# SmartBMSv2.net
KiCad netlist of a schematic drawn in EAGLE
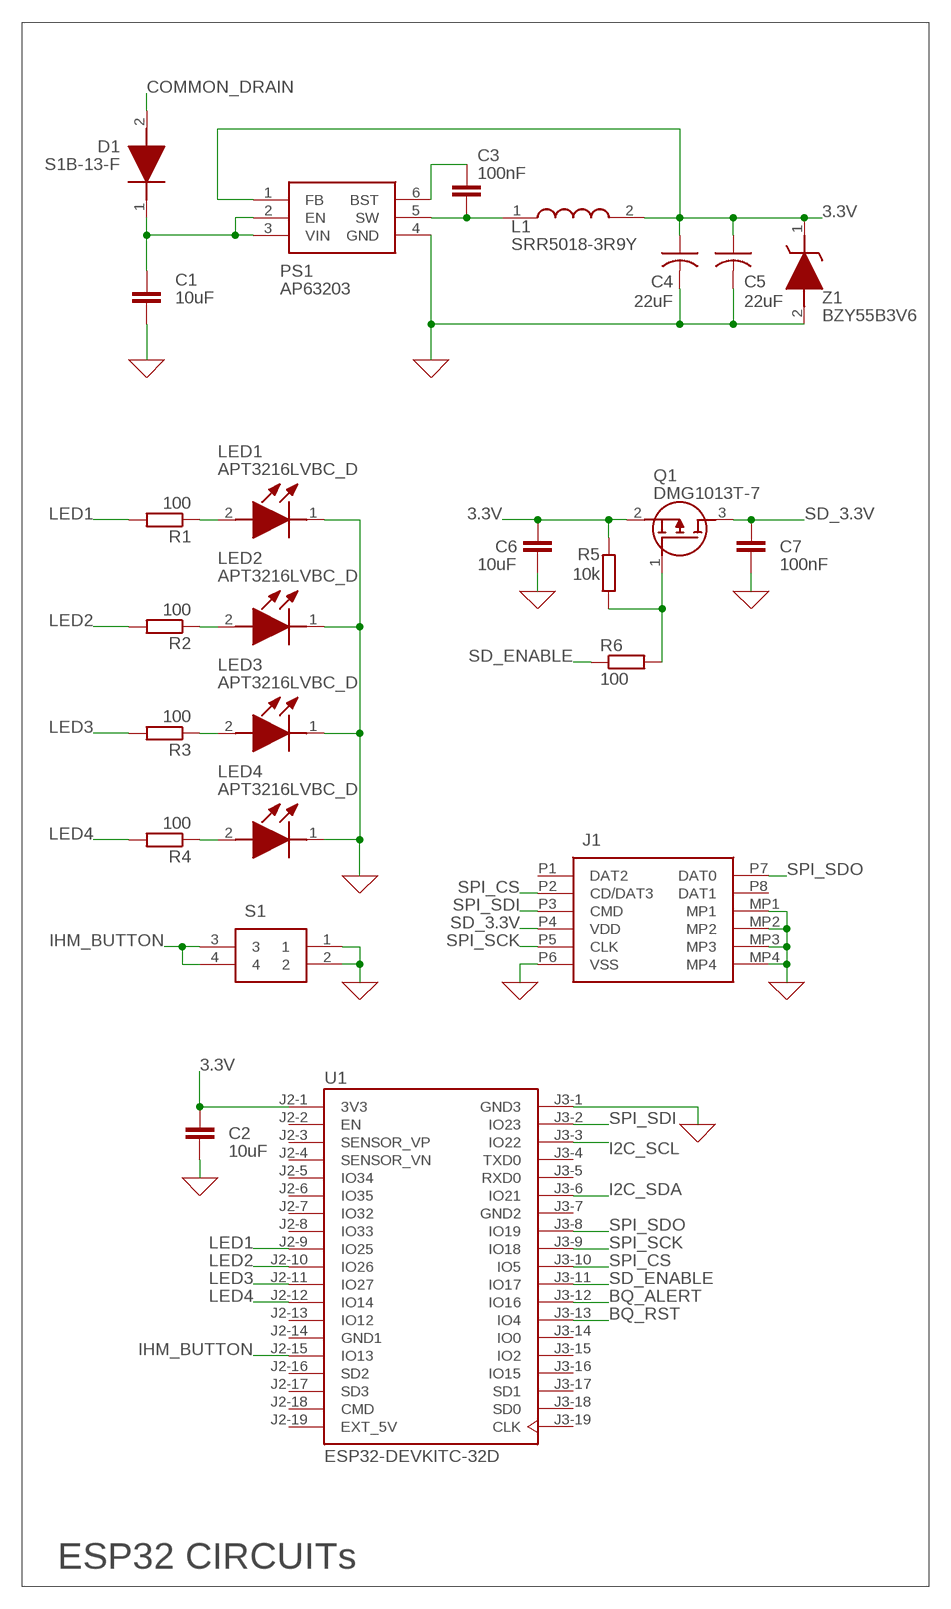
[diagram p0: schematic, sheet 1, part 1 of 2]
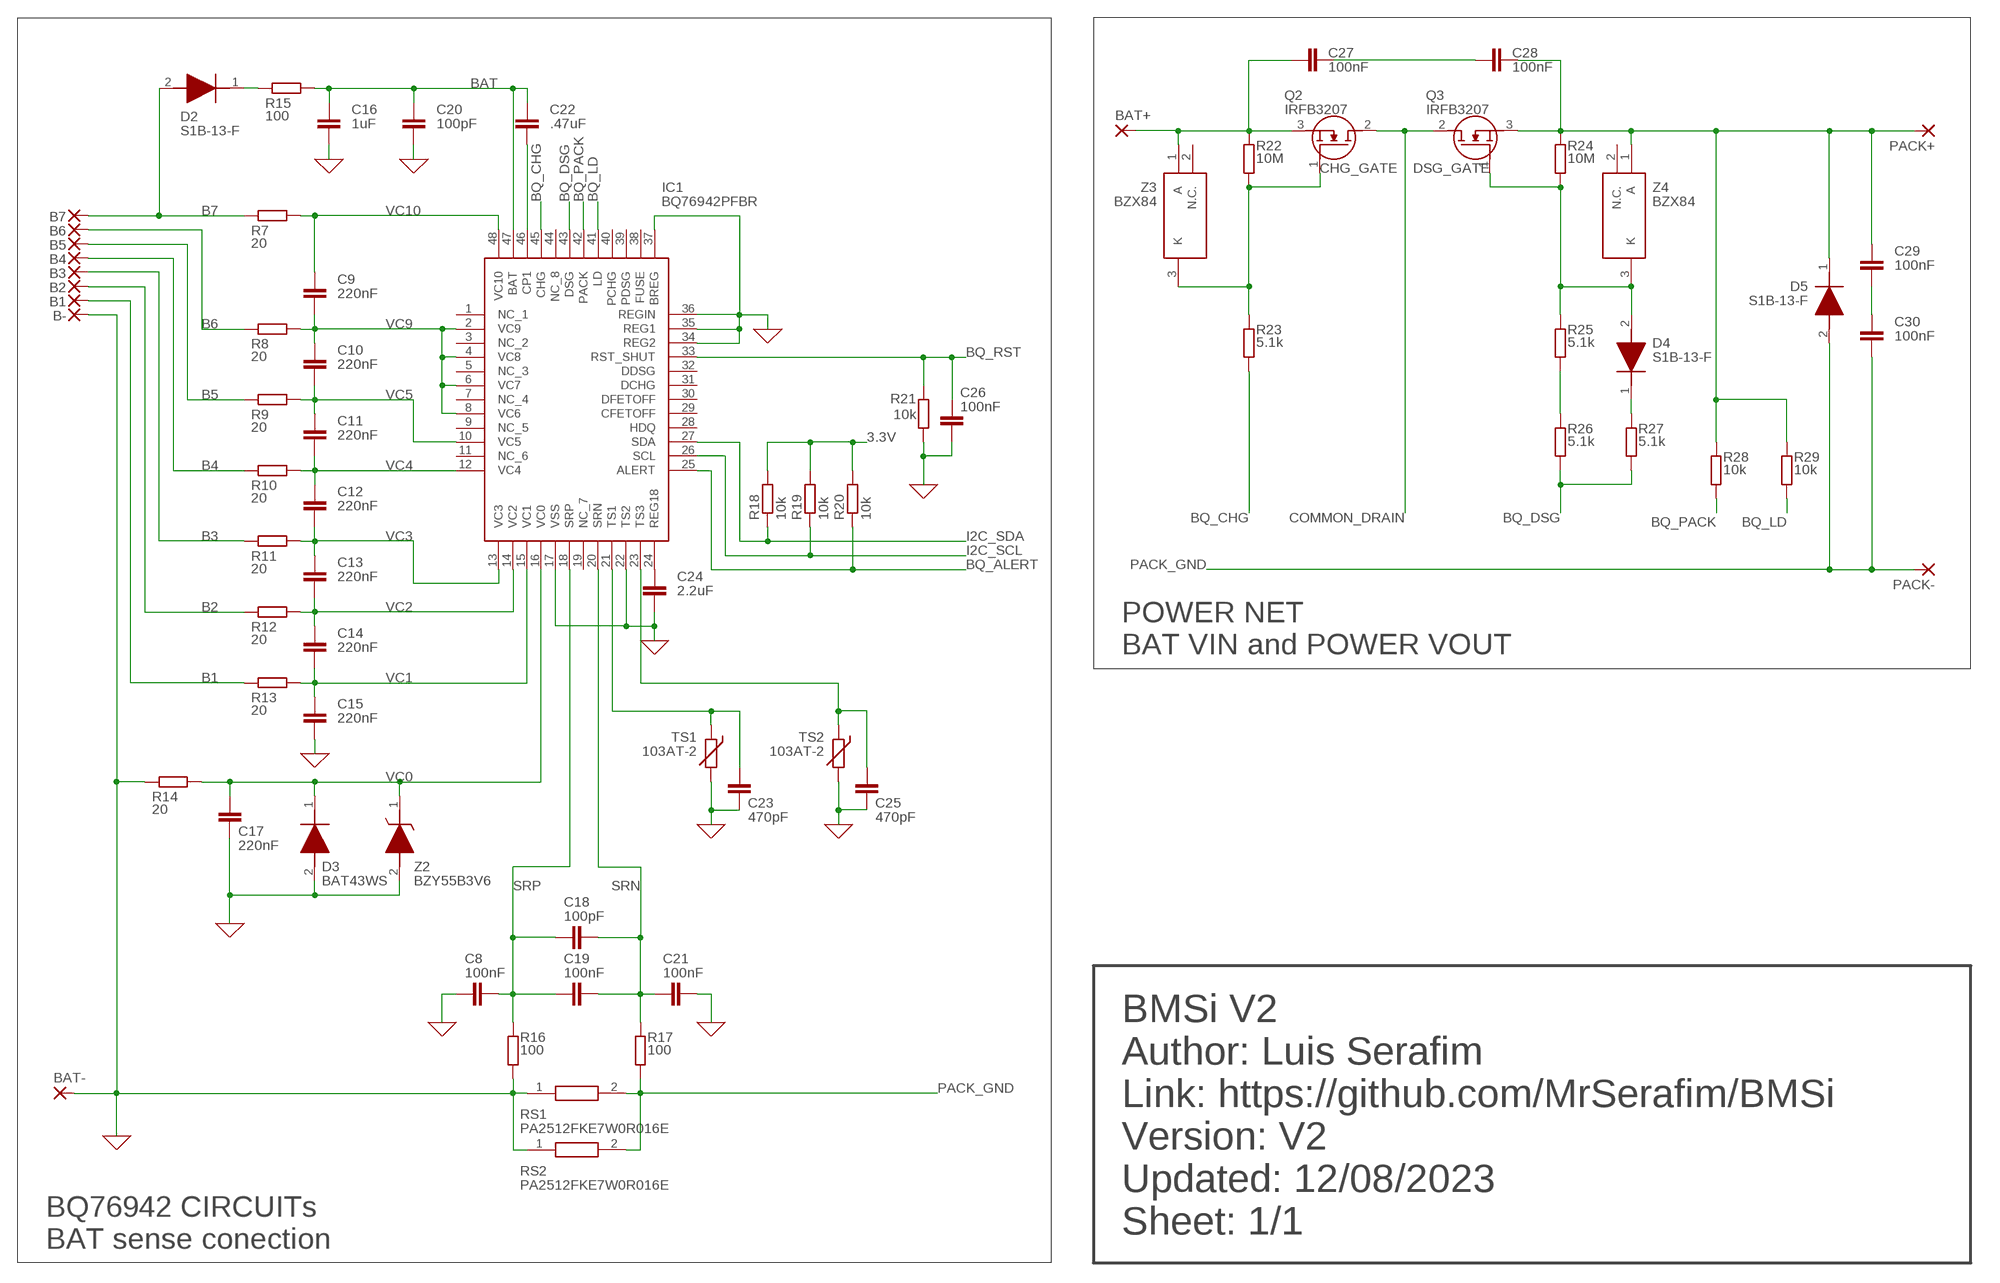
[diagram p1: schematic, sheet 1, part 2 of 2]

(export (version "E")
  (design (tool "Eeschema 10.0.6"))
  (components
    (comp (ref "B-")
      (value "SMD5")
      (footprint "eagle-import:SMD2,54-5,08")
      (libsource (lib "eagle-import") (part "SMD5"))
    )
    (comp (ref "B1")
      (value "SMD5")
      (footprint "eagle-import:SMD2,54-5,08")
      (libsource (lib "eagle-import") (part "SMD5"))
    )
    (comp (ref "B2")
      (value "SMD5")
      (footprint "eagle-import:SMD2,54-5,08")
      (libsource (lib "eagle-import") (part "SMD5"))
    )
    (comp (ref "B3")
      (value "SMD5")
      (footprint "eagle-import:SMD2,54-5,08")
      (libsource (lib "eagle-import") (part "SMD5"))
    )
    (comp (ref "B4")
      (value "SMD5")
      (footprint "eagle-import:SMD2,54-5,08")
      (libsource (lib "eagle-import") (part "SMD5"))
    )
    (comp (ref "B5")
      (value "SMD5")
      (footprint "eagle-import:SMD2,54-5,08")
      (libsource (lib "eagle-import") (part "SMD5"))
    )
    (comp (ref "B6")
      (value "SMD5")
      (footprint "eagle-import:SMD2,54-5,08")
      (libsource (lib "eagle-import") (part "SMD5"))
    )
    (comp (ref "B7")
      (value "SMD5")
      (footprint "eagle-import:SMD2,54-5,08")
      (libsource (lib "eagle-import") (part "SMD5"))
    )
    (comp (ref "BAT+")
      (value "SMD5X10")
      (footprint "eagle-import:SMD5-10")
      (libsource (lib "eagle-import") (part "SMD5X10"))
    )
    (comp (ref "BAT-")
      (value "SMD5X10")
      (footprint "eagle-import:SMD5-10")
      (libsource (lib "eagle-import") (part "SMD5X10"))
    )
    (comp (ref "C1")
      (value "10uF")
      (footprint "eagle-import:C0805")
      (libsource (lib "eagle-import") (part "C-EUC0805"))
    )
    (comp (ref "C2")
      (value "10uF")
      (footprint "eagle-import:C0805")
      (libsource (lib "eagle-import") (part "C-EUC0805"))
    )
    (comp (ref "C3")
      (value "100nF")
      (footprint "eagle-import:C0805")
      (libsource (lib "eagle-import") (part "C-EUC0805"))
    )
    (comp (ref "C4")
      (value "22uF")
      (footprint "eagle-import:C0805")
      (libsource (lib "eagle-import") (part "C-USC0805"))
    )
    (comp (ref "C5")
      (value "22uF")
      (footprint "eagle-import:C0805")
      (libsource (lib "eagle-import") (part "C-USC0805"))
    )
    (comp (ref "C6")
      (value "10uF")
      (footprint "eagle-import:C0805")
      (libsource (lib "eagle-import") (part "C-EUC0805"))
    )
    (comp (ref "C7")
      (value "100nF")
      (footprint "eagle-import:C0805")
      (libsource (lib "eagle-import") (part "C-EUC0805"))
    )
    (comp (ref "C8")
      (value "100nF")
      (footprint "eagle-import:C0805")
      (libsource (lib "eagle-import") (part "C-EUC0805"))
    )
    (comp (ref "C9")
      (value "220nF")
      (footprint "eagle-import:C0805")
      (libsource (lib "eagle-import") (part "C-EUC0805"))
    )
    (comp (ref "C10")
      (value "220nF")
      (footprint "eagle-import:C0805")
      (libsource (lib "eagle-import") (part "C-EUC0805"))
    )
    (comp (ref "C11")
      (value "220nF")
      (footprint "eagle-import:C0805")
      (libsource (lib "eagle-import") (part "C-EUC0805"))
    )
    (comp (ref "C12")
      (value "220nF")
      (footprint "eagle-import:C0805")
      (libsource (lib "eagle-import") (part "C-EUC0805"))
    )
    (comp (ref "C13")
      (value "220nF")
      (footprint "eagle-import:C0805")
      (libsource (lib "eagle-import") (part "C-EUC0805"))
    )
    (comp (ref "C14")
      (value "220nF")
      (footprint "eagle-import:C0805")
      (libsource (lib "eagle-import") (part "C-EUC0805"))
    )
    (comp (ref "C15")
      (value "220nF")
      (footprint "eagle-import:C0805")
      (libsource (lib "eagle-import") (part "C-EUC0805"))
    )
    (comp (ref "C16")
      (value "1uF")
      (footprint "eagle-import:C0805")
      (libsource (lib "eagle-import") (part "C-EUC0805"))
    )
    (comp (ref "C17")
      (value "220nF")
      (footprint "eagle-import:C0805")
      (libsource (lib "eagle-import") (part "C-EUC0805"))
    )
    (comp (ref "C18")
      (value "100pF")
      (footprint "eagle-import:C0805")
      (libsource (lib "eagle-import") (part "C-EUC0805"))
    )
    (comp (ref "C19")
      (value "100nF")
      (footprint "eagle-import:C0805")
      (libsource (lib "eagle-import") (part "C-EUC0805"))
    )
    (comp (ref "C20")
      (value "100pF")
      (footprint "eagle-import:C0805")
      (libsource (lib "eagle-import") (part "C-EUC0805"))
    )
    (comp (ref "C21")
      (value "100nF")
      (footprint "eagle-import:C0805")
      (libsource (lib "eagle-import") (part "C-EUC0805"))
    )
    (comp (ref "C22")
      (value ".47uF")
      (footprint "eagle-import:C0805")
      (libsource (lib "eagle-import") (part "C-EUC0805"))
    )
    (comp (ref "C23")
      (value "470pF")
      (footprint "eagle-import:C0805")
      (libsource (lib "eagle-import") (part "C-EUC0805"))
    )
    (comp (ref "C24")
      (value "2.2uF")
      (footprint "eagle-import:C0805")
      (libsource (lib "eagle-import") (part "C-EUC0805"))
    )
    (comp (ref "C25")
      (value "470pF")
      (footprint "eagle-import:C0805")
      (libsource (lib "eagle-import") (part "C-EUC0805"))
    )
    (comp (ref "C26")
      (value "100nF")
      (footprint "eagle-import:C0805")
      (libsource (lib "eagle-import") (part "C-EUC0805"))
    )
    (comp (ref "C27")
      (value "100nF")
      (footprint "eagle-import:C0805")
      (libsource (lib "eagle-import") (part "C-EUC0805"))
    )
    (comp (ref "C28")
      (value "100nF")
      (footprint "eagle-import:C0805")
      (libsource (lib "eagle-import") (part "C-EUC0805"))
    )
    (comp (ref "C29")
      (value "100nF")
      (footprint "eagle-import:C0805")
      (libsource (lib "eagle-import") (part "C-EUC0805"))
    )
    (comp (ref "C30")
      (value "100nF")
      (footprint "eagle-import:C0805")
      (libsource (lib "eagle-import") (part "C-EUC0805"))
    )
    (comp (ref "D1")
      (value "S1B-13-F")
      (footprint "eagle-import:DIONM5126X230N")
      (fields (field (name "MOUSER_PART_NUMBER") "621-S1B-F"))
      (libsource (lib "eagle-import") (part "S1B-13-F"))
    )
    (comp (ref "D2")
      (value "S1B-13-F")
      (footprint "eagle-import:DIONM5126X230N")
      (fields (field (name "MOUSER_PART_NUMBER") "621-S1B-F"))
      (libsource (lib "eagle-import") (part "S1B-13-F"))
    )
    (comp (ref "D3")
      (value "BAT43WS")
      (footprint "eagle-import:SOD2713X115N")
      (fields
        (field (name "MANUFACTURER_PART_NUMBER") "BAT43WS-E3-08")
        (field (name "MOUSER_PART_NUMBER") "78-BAT43WS-E3-08")
      )
      (libsource (lib "eagle-import") (part "BAT43WS-E3-08"))
    )
    (comp (ref "D4")
      (value "S1B-13-F")
      (footprint "eagle-import:DIONM5126X230N")
      (fields (field (name "MOUSER_PART_NUMBER") "621-S1B-F"))
      (libsource (lib "eagle-import") (part "S1B-13-F"))
    )
    (comp (ref "D5")
      (value "S1B-13-F")
      (footprint "eagle-import:DIONM5126X230N")
      (fields (field (name "MOUSER_PART_NUMBER") "621-S1B-F"))
      (libsource (lib "eagle-import") (part "S1B-13-F"))
    )
    (comp (ref "IC1")
      (value "BQ76942PFBR")
      (footprint "eagle-import:QFP50P900X900X120-48N")
      (fields (field (name "MOUSER_PART_NUMBER") "595-BQ76942PFBR"))
      (libsource (lib "eagle-import") (part "BQ76942PFBR"))
    )
    (comp (ref "J1")
      (value "MEM2067-02-180-00-A")
      (footprint "eagle-import:MEM20670218000A")
      (fields (field (name "MOUSER_PART_NUMBER") "640-MEM20670218000A"))
      (libsource (lib "eagle-import") (part "MEM2067-02-180-00-A"))
    )
    (comp (ref "L1")
      (value "SRR5018-3R9Y")
      (footprint "eagle-import:SRR50183R9Y")
      (fields (field (name "MOUSER_PART_NUMBER") "652-SRR5018-3R9Y"))
      (libsource (lib "eagle-import") (part "SRR5018-3R9Y"))
    )
    (comp (ref "LED1")
      (value "APT3216LVBC_D")
      (footprint "eagle-import:LEDC3216X95N")
      (fields
        (field (name "MANUFACTURER_PART_NUMBER") "APT3216LVBC/D")
        (field (name "MOUSER_PART_NUMBER") "604-APT3216LVBCD")
      )
      (libsource (lib "eagle-import") (part "APT3216LVBC_D"))
    )
    (comp (ref "LED2")
      (value "APT3216LVBC_D")
      (footprint "eagle-import:LEDC3216X95N")
      (fields
        (field (name "MANUFACTURER_PART_NUMBER") "APT3216LVBC/D")
        (field (name "MOUSER_PART_NUMBER") "604-APT3216LVBCD")
      )
      (libsource (lib "eagle-import") (part "APT3216LVBC_D"))
    )
    (comp (ref "LED3")
      (value "APT3216LVBC_D")
      (footprint "eagle-import:LEDC3216X95N")
      (fields
        (field (name "MANUFACTURER_PART_NUMBER") "APT3216LVBC/D")
        (field (name "MOUSER_PART_NUMBER") "604-APT3216LVBCD")
      )
      (libsource (lib "eagle-import") (part "APT3216LVBC_D"))
    )
    (comp (ref "LED4")
      (value "APT3216LVBC_D")
      (footprint "eagle-import:LEDC3216X95N")
      (fields
        (field (name "MANUFACTURER_PART_NUMBER") "APT3216LVBC/D")
        (field (name "MOUSER_PART_NUMBER") "604-APT3216LVBCD")
      )
      (libsource (lib "eagle-import") (part "APT3216LVBC_D"))
    )
    (comp (ref "PACK+")
      (value "SMD5X10")
      (footprint "eagle-import:SMD5-10")
      (libsource (lib "eagle-import") (part "SMD5X10"))
    )
    (comp (ref "PACK-")
      (value "SMD5X10")
      (footprint "eagle-import:SMD5-10")
      (libsource (lib "eagle-import") (part "SMD5X10"))
    )
    (comp (ref "PS1")
      (value "AP63203")
      (footprint "eagle-import:SOT95P280X100-6N")
      (fields
        (field (name "MANUFACTURER_PART_NUMBER") "AP63203WU-7")
        (field (name "MOUSER_PART_NUMBER") "621-AP63203WU-7")
      )
      (libsource (lib "eagle-import") (part "AP63203WU-7"))
    )
    (comp (ref "Q1")
      (value "DMG1013T-7")
      (footprint "eagle-import:SOT50P160X90-3N")
      (fields (field (name "MOUSER_PART_NUMBER") "621-DMG1013T-7"))
      (libsource (lib "eagle-import") (part "DMG1013T-7"))
    )
    (comp (ref "Q2")
      (value "IRFB3207")
      (footprint "eagle-import:TO220_HORIZONTAL")
      (libsource (lib "eagle-import") (part "IRFB3207PBF_HOR"))
    )
    (comp (ref "Q3")
      (value "IRFB3207")
      (footprint "eagle-import:TO220_HORIZONTAL")
      (libsource (lib "eagle-import") (part "IRFB3207PBF_HOR"))
    )
    (comp (ref "R1")
      (value "100")
      (footprint "eagle-import:R0805")
      (libsource (lib "eagle-import") (part "R-EU_R0805"))
    )
    (comp (ref "R2")
      (value "100")
      (footprint "eagle-import:R0805")
      (libsource (lib "eagle-import") (part "R-EU_R0805"))
    )
    (comp (ref "R3")
      (value "100")
      (footprint "eagle-import:R0805")
      (libsource (lib "eagle-import") (part "R-EU_R0805"))
    )
    (comp (ref "R4")
      (value "100")
      (footprint "eagle-import:R0805")
      (libsource (lib "eagle-import") (part "R-EU_R0805"))
    )
    (comp (ref "R5")
      (value "10k")
      (footprint "eagle-import:R0805")
      (libsource (lib "eagle-import") (part "R-EU_R0805"))
    )
    (comp (ref "R6")
      (value "100")
      (footprint "eagle-import:R0805")
      (libsource (lib "eagle-import") (part "R-EU_R0805"))
    )
    (comp (ref "R7")
      (value "20")
      (footprint "eagle-import:R0805")
      (libsource (lib "eagle-import") (part "R-EU_R0805"))
    )
    (comp (ref "R8")
      (value "20")
      (footprint "eagle-import:R0805")
      (libsource (lib "eagle-import") (part "R-EU_R0805"))
    )
    (comp (ref "R9")
      (value "20")
      (footprint "eagle-import:R0805")
      (libsource (lib "eagle-import") (part "R-EU_R0805"))
    )
    (comp (ref "R10")
      (value "20")
      (footprint "eagle-import:R0805")
      (libsource (lib "eagle-import") (part "R-EU_R0805"))
    )
    (comp (ref "R11")
      (value "20")
      (footprint "eagle-import:R0805")
      (libsource (lib "eagle-import") (part "R-EU_R0805"))
    )
    (comp (ref "R12")
      (value "20")
      (footprint "eagle-import:R0805")
      (libsource (lib "eagle-import") (part "R-EU_R0805"))
    )
    (comp (ref "R13")
      (value "20")
      (footprint "eagle-import:R0805")
      (libsource (lib "eagle-import") (part "R-EU_R0805"))
    )
    (comp (ref "R14")
      (value "20")
      (footprint "eagle-import:R0805")
      (libsource (lib "eagle-import") (part "R-EU_R0805"))
    )
    (comp (ref "R15")
      (value "100")
      (footprint "eagle-import:R0805")
      (libsource (lib "eagle-import") (part "R-EU_R0805"))
    )
    (comp (ref "R16")
      (value "100")
      (footprint "eagle-import:R0805")
      (libsource (lib "eagle-import") (part "R-EU_R0805"))
    )
    (comp (ref "R17")
      (value "100")
      (footprint "eagle-import:R0805")
      (libsource (lib "eagle-import") (part "R-EU_R0805"))
    )
    (comp (ref "R18")
      (value "10k")
      (footprint "eagle-import:R0805")
      (libsource (lib "eagle-import") (part "R-EU_R0805"))
    )
    (comp (ref "R19")
      (value "10k")
      (footprint "eagle-import:R0805")
      (libsource (lib "eagle-import") (part "R-EU_R0805"))
    )
    (comp (ref "R20")
      (value "10k")
      (footprint "eagle-import:R0805")
      (libsource (lib "eagle-import") (part "R-EU_R0805"))
    )
    (comp (ref "R21")
      (value "10k")
      (footprint "eagle-import:R0805")
      (libsource (lib "eagle-import") (part "R-EU_R0805"))
    )
    (comp (ref "R22")
      (value "10M")
      (footprint "eagle-import:R0805")
      (libsource (lib "eagle-import") (part "R-EU_R0805"))
    )
    (comp (ref "R23")
      (value "5.1k")
      (footprint "eagle-import:R0805")
      (libsource (lib "eagle-import") (part "R-EU_R0805"))
    )
    (comp (ref "R24")
      (value "10M")
      (footprint "eagle-import:R0805")
      (libsource (lib "eagle-import") (part "R-EU_R0805"))
    )
    (comp (ref "R25")
      (value "5.1k")
      (footprint "eagle-import:R0805")
      (libsource (lib "eagle-import") (part "R-EU_R0805"))
    )
    (comp (ref "R26")
      (value "5.1k")
      (footprint "eagle-import:R0805")
      (libsource (lib "eagle-import") (part "R-EU_R0805"))
    )
    (comp (ref "R27")
      (value "5.1k")
      (footprint "eagle-import:R0805")
      (libsource (lib "eagle-import") (part "R-EU_R0805"))
    )
    (comp (ref "R28")
      (value "10k")
      (footprint "eagle-import:R0805")
      (libsource (lib "eagle-import") (part "R-EU_R0805"))
    )
    (comp (ref "R29")
      (value "10k")
      (footprint "eagle-import:R0805")
      (libsource (lib "eagle-import") (part "R-EU_R0805"))
    )
    (comp (ref "RS1")
      (value "PA2512FKE7W0R016E")
      (footprint "eagle-import:RESC6432X88N")
      (libsource (lib "eagle-import") (part "PA2512FKE7W0R016E"))
    )
    (comp (ref "RS2")
      (value "PA2512FKE7W0R016E")
      (footprint "eagle-import:RESC6432X88N")
      (libsource (lib "eagle-import") (part "PA2512FKE7W0R016E"))
    )
    (comp (ref "S1")
      (value "FSM2JSMAATR")
      (footprint "eagle-import:FSM2J_1")
      (fields (field (name "MOUSER_PART_NUMBER") "506-FSM2JSMAATR"))
      (libsource (lib "eagle-import") (part "FSM2JSMAATR"))
    )
    (comp (ref "TS1")
      (value "103AT-2")
      (footprint "eagle-import:RS-2,5")
      (libsource (lib "eagle-import") (part "THERMISTOR-2,5"))
    )
    (comp (ref "TS2")
      (value "103AT-2")
      (footprint "eagle-import:RS-2,5")
      (libsource (lib "eagle-import") (part "THERMISTOR-2,5"))
    )
    (comp (ref "U1")
      (value "ESP32-DEVKITC-32D")
      (footprint "eagle-import:MODULE_ESP32-DEVKITC-32D")
      (fields (field (name "MF") "Espressif Systems"))
      (libsource (lib "eagle-import") (part "ESP32-DEVKITC-32D"))
    )
    (comp (ref "Z1")
      (value "BZY55B3V6")
      (footprint "eagle-import:DIOC2012X85N")
      (fields
        (field (name "MANUFACTURER_PART_NUMBER") "BZY55B3V6 RBG")
        (field (name "MOUSER_PART_NUMBER") "821-BZY55B3V6RBG")
      )
      (libsource (lib "eagle-import") (part "BZY55B3V6_RBG"))
    )
    (comp (ref "Z2")
      (value "BZY55B3V6")
      (footprint "eagle-import:DIOC2012X85N")
      (fields
        (field (name "MANUFACTURER_PART_NUMBER") "BZY55B3V6 RBG")
        (field (name "MOUSER_PART_NUMBER") "821-BZY55B3V6RBG")
      )
      (libsource (lib "eagle-import") (part "BZY55B3V6_RBG"))
    )
    (comp (ref "Z3")
      (value "BZX84")
      (footprint "eagle-import:SOT95P230X110-3N")
      (fields
        (field (name "MANUFACTURER_PART_NUMBER") "BZX84-C16,215")
        (field (name "MOUSER_PART_NUMBER") "771-BZX84-C16-T/R")
      )
      (libsource (lib "eagle-import") (part "BZX84-C16,215"))
    )
    (comp (ref "Z4")
      (value "BZX84")
      (footprint "eagle-import:SOT95P230X110-3N")
      (fields
        (field (name "MANUFACTURER_PART_NUMBER") "BZX84-C16,215")
        (field (name "MOUSER_PART_NUMBER") "771-BZX84-C16-T/R")
      )
      (libsource (lib "eagle-import") (part "BZX84-C16,215"))
    )
  )
  (nets
    (net (code "1") (name "/3.3V") (class "Default")
      (node (ref "C2") (pin "1") (pinfunction "1_1") (pintype "passive"))
      (node (ref "C4") (pin "1") (pinfunction "1_1") (pintype "passive"))
      (node (ref "C5") (pin "1") (pinfunction "1_1") (pintype "passive"))
      (node (ref "C6") (pin "2") (pinfunction "2_2") (pintype "passive"))
      (node (ref "L1") (pin "2") (pinfunction "2_2") (pintype "bidirectional"))
      (node (ref "PS1") (pin "1") (pinfunction "FB_1") (pintype "input"))
      (node (ref "Q1") (pin "2") (pinfunction "S_2") (pintype "bidirectional"))
      (node (ref "R18") (pin "2") (pinfunction "2_2") (pintype "passive"))
      (node (ref "R19") (pin "2") (pinfunction "2_2") (pintype "passive"))
      (node (ref "R20") (pin "2") (pinfunction "2_2") (pintype "passive"))
      (node (ref "R5") (pin "2") (pinfunction "2_2") (pintype "passive"))
      (node (ref "U1") (pin "J2-1") (pinfunction "3V3_J2-1") (pintype "power_in"))
      (node (ref "Z1") (pin "1") (pinfunction "K_1") (pintype "bidirectional"))
    )
    (net (code "2") (name "/B1") (class "Default")
      (node (ref "B1") (pin "1") (pinfunction "P_1") (pintype "passive"))
      (node (ref "R13") (pin "1") (pinfunction "1_1") (pintype "passive"))
    )
    (net (code "3") (name "/B2") (class "Default")
      (node (ref "B2") (pin "1") (pinfunction "P_1") (pintype "passive"))
      (node (ref "R12") (pin "1") (pinfunction "1_1") (pintype "passive"))
    )
    (net (code "4") (name "/B3") (class "Default")
      (node (ref "B3") (pin "1") (pinfunction "P_1") (pintype "passive"))
      (node (ref "R11") (pin "1") (pinfunction "1_1") (pintype "passive"))
    )
    (net (code "5") (name "/B4") (class "Default")
      (node (ref "B4") (pin "1") (pinfunction "P_1") (pintype "passive"))
      (node (ref "R10") (pin "1") (pinfunction "1_1") (pintype "passive"))
    )
    (net (code "6") (name "/B5") (class "Default")
      (node (ref "B5") (pin "1") (pinfunction "P_1") (pintype "passive"))
      (node (ref "R9") (pin "1") (pinfunction "1_1") (pintype "passive"))
    )
    (net (code "7") (name "/B6") (class "Default")
      (node (ref "B6") (pin "1") (pinfunction "P_1") (pintype "passive"))
      (node (ref "R8") (pin "1") (pinfunction "1_1") (pintype "passive"))
    )
    (net (code "8") (name "/B7") (class "Default")
      (node (ref "B7") (pin "1") (pinfunction "P_1") (pintype "passive"))
      (node (ref "D2") (pin "2") (pinfunction "A_2") (pintype "bidirectional"))
      (node (ref "R7") (pin "1") (pinfunction "1_1") (pintype "passive"))
    )
    (net (code "9") (name "/BAT") (class "Default")
      (node (ref "C16") (pin "1") (pinfunction "1_1") (pintype "passive"))
      (node (ref "C20") (pin "1") (pinfunction "1_1") (pintype "passive"))
      (node (ref "C22") (pin "1") (pinfunction "1_1") (pintype "passive"))
      (node (ref "IC1") (pin "47") (pinfunction "BAT_47") (pintype "bidirectional"))
      (node (ref "R15") (pin "2") (pinfunction "2_2") (pintype "passive"))
    )
    (net (code "10") (name "/BQ_ALERT") (class "Default")
      (node (ref "IC1") (pin "25") (pinfunction "ALERT_25") (pintype "bidirectional"))
      (node (ref "R20") (pin "1") (pinfunction "1_1") (pintype "passive"))
      (node (ref "U1") (pin "J3-12") (pinfunction "IO16_J3-12") (pintype "bidirectional"))
    )
    (net (code "11") (name "/BQ_CHG") (class "Default")
      (node (ref "IC1") (pin "45") (pinfunction "CHG_45") (pintype "bidirectional"))
      (node (ref "R23") (pin "1") (pinfunction "1_1") (pintype "passive"))
    )
    (net (code "12") (name "/BQ_DSG") (class "Default")
      (node (ref "IC1") (pin "43") (pinfunction "DSG_43") (pintype "bidirectional"))
      (node (ref "R26") (pin "1") (pinfunction "1_1") (pintype "passive"))
      (node (ref "R27") (pin "1") (pinfunction "1_1") (pintype "passive"))
    )
    (net (code "13") (name "/BQ_LD") (class "Default")
      (node (ref "IC1") (pin "41") (pinfunction "LD_41") (pintype "bidirectional"))
      (node (ref "R29") (pin "2") (pinfunction "2_2") (pintype "passive"))
    )
    (net (code "14") (name "/BQ_PACK") (class "Default")
      (node (ref "IC1") (pin "42") (pinfunction "PACK_42") (pintype "bidirectional"))
      (node (ref "R28") (pin "2") (pinfunction "2_2") (pintype "passive"))
    )
    (net (code "15") (name "/BQ_RST") (class "Default")
      (node (ref "C26") (pin "1") (pinfunction "1_1") (pintype "passive"))
      (node (ref "IC1") (pin "33") (pinfunction "RST_SHUT_33") (pintype "bidirectional"))
      (node (ref "R21") (pin "2") (pinfunction "2_2") (pintype "passive"))
      (node (ref "U1") (pin "J3-13") (pinfunction "IO4_J3-13") (pintype "bidirectional"))
    )
    (net (code "16") (name "/CHG_GATE") (class "Default")
      (node (ref "Q2") (pin "1") (pinfunction "G_1") (pintype "bidirectional"))
      (node (ref "R22") (pin "1") (pinfunction "1_1") (pintype "passive"))
      (node (ref "R23") (pin "2") (pinfunction "2_2") (pintype "passive"))
      (node (ref "Z3") (pin "3") (pinfunction "K_3") (pintype "bidirectional"))
    )
    (net (code "17") (name "/COMMON_DRAIN") (class "Default")
      (node (ref "D1") (pin "2") (pinfunction "A_2") (pintype "bidirectional"))
      (node (ref "Q2") (pin "2") (pinfunction "D_2") (pintype "bidirectional"))
      (node (ref "Q3") (pin "2") (pinfunction "D_2") (pintype "bidirectional"))
    )
    (net (code "18") (name "/DSG_GATE") (class "Default")
      (node (ref "D4") (pin "2") (pinfunction "A_2") (pintype "bidirectional"))
      (node (ref "Q3") (pin "1") (pinfunction "G_1") (pintype "bidirectional"))
      (node (ref "R24") (pin "1") (pinfunction "1_1") (pintype "passive"))
      (node (ref "R25") (pin "2") (pinfunction "2_2") (pintype "passive"))
      (node (ref "Z4") (pin "3") (pinfunction "K_3") (pintype "bidirectional"))
    )
    (net (code "19") (name "/EXT_5V") (class "Default")
      (node (ref "U1") (pin "J2-19") (pinfunction "EXT_5V_J2-19") (pintype "power_in"))
    )
    (net (code "20") (name "/GND1") (class "Default")
      (node (ref "U1") (pin "J2-14") (pinfunction "GND1_J2-14") (pintype "power_in"))
    )
    (net (code "21") (name "/GND2") (class "Default")
      (node (ref "U1") (pin "J3-7") (pinfunction "GND2_J3-7") (pintype "power_in"))
    )
    (net (code "22") (name "/I2C_SCL") (class "Default")
      (node (ref "IC1") (pin "26") (pinfunction "SCL_26") (pintype "bidirectional"))
      (node (ref "R19") (pin "1") (pinfunction "1_1") (pintype "passive"))
      (node (ref "U1") (pin "J3-3") (pinfunction "IO22_J3-3") (pintype "bidirectional"))
    )
    (net (code "23") (name "/I2C_SDA") (class "Default")
      (node (ref "IC1") (pin "27") (pinfunction "SDA_27") (pintype "bidirectional"))
      (node (ref "R18") (pin "1") (pinfunction "1_1") (pintype "passive"))
      (node (ref "U1") (pin "J3-6") (pinfunction "IO21_J3-6") (pintype "bidirectional"))
    )
    (net (code "24") (name "/IHM_BUTTON") (class "Default")
      (node (ref "S1") (pin "3") (pinfunction "3_3") (pintype "bidirectional"))
      (node (ref "S1") (pin "4") (pinfunction "4_4") (pintype "bidirectional"))
      (node (ref "U1") (pin "J2-15") (pinfunction "IO13_J2-15") (pintype "bidirectional"))
    )
    (net (code "25") (name "/LED1") (class "Default")
      (node (ref "R1") (pin "2") (pinfunction "2_2") (pintype "passive"))
      (node (ref "U1") (pin "J2-9") (pinfunction "IO25_J2-9") (pintype "bidirectional"))
    )
    (net (code "26") (name "/LED2") (class "Default")
      (node (ref "R2") (pin "2") (pinfunction "2_2") (pintype "passive"))
      (node (ref "U1") (pin "J2-10") (pinfunction "IO26_J2-10") (pintype "bidirectional"))
    )
    (net (code "27") (name "/LED3") (class "Default")
      (node (ref "R3") (pin "2") (pinfunction "2_2") (pintype "passive"))
      (node (ref "U1") (pin "J2-11") (pinfunction "IO27_J2-11") (pintype "bidirectional"))
    )
    (net (code "28") (name "/LED4") (class "Default")
      (node (ref "R4") (pin "2") (pinfunction "2_2") (pintype "passive"))
      (node (ref "U1") (pin "J2-12") (pinfunction "IO14_J2-12") (pintype "bidirectional"))
    )
    (net (code "29") (name "/PACK_GND") (class "Default")
      (node (ref "C30") (pin "2") (pinfunction "2_2") (pintype "passive"))
      (node (ref "D5") (pin "2") (pinfunction "A_2") (pintype "bidirectional"))
      (node (ref "PACK-") (pin "1") (pinfunction "P_1") (pintype "passive"))
      (node (ref "R17") (pin "1") (pinfunction "1_1") (pintype "passive"))
      (node (ref "RS1") (pin "2") (pinfunction "2_2") (pintype "bidirectional"))
      (node (ref "RS2") (pin "2") (pinfunction "2_2") (pintype "bidirectional"))
    )
    (net (code "30") (name "/SD_3.3V") (class "Default")
      (node (ref "C7") (pin "2") (pinfunction "2_2") (pintype "passive"))
      (node (ref "J1") (pin "P4") (pinfunction "VDD_P4") (pintype "bidirectional"))
      (node (ref "Q1") (pin "3") (pinfunction "D_3") (pintype "bidirectional"))
    )
    (net (code "31") (name "/SD_ENABLE") (class "Default")
      (node (ref "R6") (pin "1") (pinfunction "1_1") (pintype "passive"))
      (node (ref "U1") (pin "J3-11") (pinfunction "IO17_J3-11") (pintype "bidirectional"))
    )
    (net (code "32") (name "/SPI_CS") (class "Default")
      (node (ref "J1") (pin "P2") (pinfunction "CD/DAT3_P2") (pintype "bidirectional"))
      (node (ref "U1") (pin "J3-10") (pinfunction "IO5_J3-10") (pintype "bidirectional"))
    )
    (net (code "33") (name "/SPI_SCK") (class "Default")
      (node (ref "J1") (pin "P5") (pinfunction "CLK_P5") (pintype "bidirectional"))
      (node (ref "U1") (pin "J3-9") (pinfunction "IO18_J3-9") (pintype "bidirectional"))
    )
    (net (code "34") (name "/SPI_SDI") (class "Default")
      (node (ref "J1") (pin "P3") (pinfunction "CMD_P3") (pintype "bidirectional"))
      (node (ref "U1") (pin "J3-2") (pinfunction "IO23_J3-2") (pintype "bidirectional"))
    )
    (net (code "35") (name "/SPI_SDO") (class "Default")
      (node (ref "J1") (pin "P7") (pinfunction "DAT0_P7") (pintype "bidirectional"))
      (node (ref "U1") (pin "J3-8") (pinfunction "IO19_J3-8") (pintype "bidirectional"))
    )
    (net (code "36") (name "/SRN") (class "Default")
      (node (ref "C18") (pin "2") (pinfunction "2_2") (pintype "passive"))
      (node (ref "C19") (pin "2") (pinfunction "2_2") (pintype "passive"))
      (node (ref "C21") (pin "1") (pinfunction "1_1") (pintype "passive"))
      (node (ref "IC1") (pin "20") (pinfunction "SRN_20") (pintype "bidirectional"))
      (node (ref "R17") (pin "2") (pinfunction "2_2") (pintype "passive"))
    )
    (net (code "37") (name "/SRP") (class "Default")
      (node (ref "C18") (pin "1") (pinfunction "1_1") (pintype "passive"))
      (node (ref "C19") (pin "1") (pinfunction "1_1") (pintype "passive"))
      (node (ref "C8") (pin "2") (pinfunction "2_2") (pintype "passive"))
      (node (ref "IC1") (pin "18") (pinfunction "SRP_18") (pintype "bidirectional"))
      (node (ref "R16") (pin "2") (pinfunction "2_2") (pintype "passive"))
    )
    (net (code "38") (name "/VC0") (class "Default")
      (node (ref "C17") (pin "1") (pinfunction "1_1") (pintype "passive"))
      (node (ref "D3") (pin "1") (pinfunction "K_1") (pintype "bidirectional"))
      (node (ref "IC1") (pin "16") (pinfunction "VC0_16") (pintype "bidirectional"))
      (node (ref "R14") (pin "2") (pinfunction "2_2") (pintype "passive"))
      (node (ref "Z2") (pin "1") (pinfunction "K_1") (pintype "bidirectional"))
    )
    (net (code "39") (name "/VC1") (class "Default")
      (node (ref "C14") (pin "2") (pinfunction "2_2") (pintype "passive"))
      (node (ref "C15") (pin "1") (pinfunction "1_1") (pintype "passive"))
      (node (ref "IC1") (pin "15") (pinfunction "VC1_15") (pintype "bidirectional"))
      (node (ref "R13") (pin "2") (pinfunction "2_2") (pintype "passive"))
    )
    (net (code "40") (name "/VC2") (class "Default")
      (node (ref "C13") (pin "2") (pinfunction "2_2") (pintype "passive"))
      (node (ref "C14") (pin "1") (pinfunction "1_1") (pintype "passive"))
      (node (ref "IC1") (pin "14") (pinfunction "VC2_14") (pintype "bidirectional"))
      (node (ref "R12") (pin "2") (pinfunction "2_2") (pintype "passive"))
    )
    (net (code "41") (name "/VC3") (class "Default")
      (node (ref "C12") (pin "2") (pinfunction "2_2") (pintype "passive"))
      (node (ref "C13") (pin "1") (pinfunction "1_1") (pintype "passive"))
      (node (ref "IC1") (pin "13") (pinfunction "VC3_13") (pintype "bidirectional"))
      (node (ref "R11") (pin "2") (pinfunction "2_2") (pintype "passive"))
    )
    (net (code "42") (name "/VC4") (class "Default")
      (node (ref "C11") (pin "2") (pinfunction "2_2") (pintype "passive"))
      (node (ref "C12") (pin "1") (pinfunction "1_1") (pintype "passive"))
      (node (ref "IC1") (pin "12") (pinfunction "VC4_12") (pintype "bidirectional"))
      (node (ref "R10") (pin "2") (pinfunction "2_2") (pintype "passive"))
    )
    (net (code "43") (name "/VC5") (class "Default")
      (node (ref "C10") (pin "2") (pinfunction "2_2") (pintype "passive"))
      (node (ref "C11") (pin "1") (pinfunction "1_1") (pintype "passive"))
      (node (ref "IC1") (pin "10") (pinfunction "VC5_10") (pintype "bidirectional"))
      (node (ref "R9") (pin "2") (pinfunction "2_2") (pintype "passive"))
    )
    (net (code "44") (name "/VC9") (class "Default")
      (node (ref "C10") (pin "1") (pinfunction "1_1") (pintype "passive"))
      (node (ref "C9") (pin "2") (pinfunction "2_2") (pintype "passive"))
      (node (ref "IC1") (pin "2") (pinfunction "VC9_2") (pintype "bidirectional"))
      (node (ref "IC1") (pin "4") (pinfunction "VC8_4") (pintype "bidirectional"))
      (node (ref "IC1") (pin "6") (pinfunction "VC7_6") (pintype "bidirectional"))
      (node (ref "IC1") (pin "8") (pinfunction "VC6_8") (pintype "bidirectional"))
      (node (ref "R8") (pin "2") (pinfunction "2_2") (pintype "passive"))
    )
    (net (code "45") (name "/VC10") (class "Default")
      (node (ref "C9") (pin "1") (pinfunction "1_1") (pintype "passive"))
      (node (ref "IC1") (pin "48") (pinfunction "VC10_48") (pintype "bidirectional"))
      (node (ref "R7") (pin "2") (pinfunction "2_2") (pintype "passive"))
    )
    (net (code "46") (name "GND") (class "Default")
      (node (ref "B-") (pin "1") (pinfunction "P_1") (pintype "passive"))
      (node (ref "BAT-") (pin "1") (pinfunction "P_1") (pintype "passive"))
      (node (ref "C1") (pin "2") (pinfunction "2_2") (pintype "passive"))
      (node (ref "C15") (pin "2") (pinfunction "2_2") (pintype "passive"))
      (node (ref "C16") (pin "2") (pinfunction "2_2") (pintype "passive"))
      (node (ref "C17") (pin "2") (pinfunction "2_2") (pintype "passive"))
      (node (ref "C2") (pin "2") (pinfunction "2_2") (pintype "passive"))
      (node (ref "C20") (pin "2") (pinfunction "2_2") (pintype "passive"))
      (node (ref "C21") (pin "2") (pinfunction "2_2") (pintype "passive"))
      (node (ref "C23") (pin "2") (pinfunction "2_2") (pintype "passive"))
      (node (ref "C24") (pin "2") (pinfunction "2_2") (pintype "passive"))
      (node (ref "C25") (pin "2") (pinfunction "2_2") (pintype "passive"))
      (node (ref "C26") (pin "2") (pinfunction "2_2") (pintype "passive"))
      (node (ref "C4") (pin "2") (pinfunction "2_2") (pintype "passive"))
      (node (ref "C5") (pin "2") (pinfunction "2_2") (pintype "passive"))
      (node (ref "C6") (pin "1") (pinfunction "1_1") (pintype "passive"))
      (node (ref "C7") (pin "1") (pinfunction "1_1") (pintype "passive"))
      (node (ref "C8") (pin "1") (pinfunction "1_1") (pintype "passive"))
      (node (ref "D3") (pin "2") (pinfunction "A_2") (pintype "bidirectional"))
      (node (ref "IC1") (pin "17") (pinfunction "VSS_17") (pintype "bidirectional"))
      (node (ref "IC1") (pin "22") (pinfunction "TS2_22") (pintype "bidirectional"))
      (node (ref "IC1") (pin "34") (pinfunction "REG2_34") (pintype "bidirectional"))
      (node (ref "IC1") (pin "35") (pinfunction "REG1_35") (pintype "bidirectional"))
      (node (ref "IC1") (pin "36") (pinfunction "REGIN_36") (pintype "bidirectional"))
      (node (ref "IC1") (pin "37") (pinfunction "BREG_37") (pintype "bidirectional"))
      (node (ref "J1") (pin "MP1") (pinfunction "MP1_MP1") (pintype "bidirectional"))
      (node (ref "J1") (pin "MP2") (pinfunction "MP2_MP2") (pintype "bidirectional"))
      (node (ref "J1") (pin "MP3") (pinfunction "MP3_MP3") (pintype "bidirectional"))
      (node (ref "J1") (pin "MP4") (pinfunction "MP4_MP4") (pintype "bidirectional"))
      (node (ref "J1") (pin "P6") (pinfunction "VSS_P6") (pintype "bidirectional"))
      (node (ref "LED1") (pin "1") (pinfunction "K_1") (pintype "bidirectional"))
      (node (ref "LED2") (pin "1") (pinfunction "K_1") (pintype "bidirectional"))
      (node (ref "LED3") (pin "1") (pinfunction "K_1") (pintype "bidirectional"))
      (node (ref "LED4") (pin "1") (pinfunction "K_1") (pintype "bidirectional"))
      (node (ref "PS1") (pin "4") (pinfunction "GND_4") (pintype "power_in"))
      (node (ref "R14") (pin "1") (pinfunction "1_1") (pintype "passive"))
      (node (ref "R16") (pin "1") (pinfunction "1_1") (pintype "passive"))
      (node (ref "R21") (pin "1") (pinfunction "1_1") (pintype "passive"))
      (node (ref "RS1") (pin "1") (pinfunction "1_1") (pintype "bidirectional"))
      (node (ref "RS2") (pin "1") (pinfunction "1_1") (pintype "bidirectional"))
      (node (ref "S1") (pin "1") (pinfunction "1_1") (pintype "bidirectional"))
      (node (ref "S1") (pin "2") (pinfunction "2_2") (pintype "bidirectional"))
      (node (ref "TS1") (pin "2") (pinfunction "2_2") (pintype "passive"))
      (node (ref "TS2") (pin "2") (pinfunction "2_2") (pintype "passive"))
      (node (ref "U1") (pin "J3-1") (pinfunction "GND3_J3-1") (pintype "power_in"))
      (node (ref "Z1") (pin "2") (pinfunction "A_2") (pintype "bidirectional"))
      (node (ref "Z2") (pin "2") (pinfunction "A_2") (pintype "bidirectional"))
    )
    (net (code "47") (name "Net-(BAT+-P)") (class "Default")
      (node (ref "BAT+") (pin "1") (pinfunction "P_1") (pintype "passive"))
      (node (ref "C27") (pin "1") (pinfunction "1_1") (pintype "passive"))
      (node (ref "Q2") (pin "3") (pinfunction "S_3") (pintype "bidirectional"))
      (node (ref "R22") (pin "2") (pinfunction "2_2") (pintype "passive"))
      (node (ref "Z3") (pin "1") (pinfunction "A_1") (pintype "bidirectional"))
    )
    (net (code "48") (name "Net-(C27-Pad2)") (class "Default")
      (node (ref "C27") (pin "2") (pinfunction "2_2") (pintype "passive"))
      (node (ref "C28") (pin "1") (pinfunction "1_1") (pintype "passive"))
    )
    (net (code "49") (name "Net-(C29-Pad2)") (class "Default")
      (node (ref "C29") (pin "2") (pinfunction "2_2") (pintype "passive"))
      (node (ref "C30") (pin "1") (pinfunction "1_1") (pintype "passive"))
    )
    (net (code "50") (name "Net-(D1-K)") (class "Default")
      (node (ref "C1") (pin "1") (pinfunction "1_1") (pintype "passive"))
      (node (ref "D1") (pin "1") (pinfunction "K_1") (pintype "bidirectional"))
      (node (ref "PS1") (pin "2") (pinfunction "EN_2") (pintype "input"))
      (node (ref "PS1") (pin "3") (pinfunction "VIN_3") (pintype "power_in"))
    )
    (net (code "51") (name "Net-(D2-K)") (class "Default")
      (node (ref "D2") (pin "1") (pinfunction "K_1") (pintype "bidirectional"))
      (node (ref "R15") (pin "1") (pinfunction "1_1") (pintype "passive"))
    )
    (net (code "52") (name "Net-(D4-K)") (class "Default")
      (node (ref "D4") (pin "1") (pinfunction "K_1") (pintype "bidirectional"))
      (node (ref "R27") (pin "2") (pinfunction "2_2") (pintype "passive"))
    )
    (net (code "53") (name "Net-(D5-K)") (class "Default")
      (node (ref "C28") (pin "2") (pinfunction "2_2") (pintype "passive"))
      (node (ref "C29") (pin "1") (pinfunction "1_1") (pintype "passive"))
      (node (ref "D5") (pin "1") (pinfunction "K_1") (pintype "bidirectional"))
      (node (ref "PACK+") (pin "1") (pinfunction "P_1") (pintype "passive"))
      (node (ref "Q3") (pin "3") (pinfunction "S_3") (pintype "bidirectional"))
      (node (ref "R24") (pin "2") (pinfunction "2_2") (pintype "passive"))
      (node (ref "R28") (pin "1") (pinfunction "1_1") (pintype "passive"))
      (node (ref "R29") (pin "1") (pinfunction "1_1") (pintype "passive"))
      (node (ref "Z4") (pin "1") (pinfunction "A_1") (pintype "bidirectional"))
    )
    (net (code "54") (name "Net-(IC1-CP1)") (class "Default")
      (node (ref "C22") (pin "2") (pinfunction "2_2") (pintype "passive"))
      (node (ref "IC1") (pin "46") (pinfunction "CP1_46") (pintype "bidirectional"))
    )
    (net (code "55") (name "Net-(IC1-REG18)") (class "Default")
      (node (ref "C24") (pin "1") (pinfunction "1_1") (pintype "passive"))
      (node (ref "IC1") (pin "24") (pinfunction "REG18_24") (pintype "bidirectional"))
    )
    (net (code "56") (name "Net-(IC1-TS1)") (class "Default")
      (node (ref "C23") (pin "1") (pinfunction "1_1") (pintype "passive"))
      (node (ref "IC1") (pin "21") (pinfunction "TS1_21") (pintype "bidirectional"))
      (node (ref "TS1") (pin "1") (pinfunction "1_1") (pintype "passive"))
    )
    (net (code "57") (name "Net-(IC1-TS3)") (class "Default")
      (node (ref "C25") (pin "1") (pinfunction "1_1") (pintype "passive"))
      (node (ref "IC1") (pin "23") (pinfunction "TS3_23") (pintype "bidirectional"))
      (node (ref "TS2") (pin "1") (pinfunction "1_1") (pintype "passive"))
    )
    (net (code "58") (name "Net-(LED1-A)") (class "Default")
      (node (ref "LED1") (pin "2") (pinfunction "A_2") (pintype "bidirectional"))
      (node (ref "R1") (pin "1") (pinfunction "1_1") (pintype "passive"))
    )
    (net (code "59") (name "Net-(LED2-A)") (class "Default")
      (node (ref "LED2") (pin "2") (pinfunction "A_2") (pintype "bidirectional"))
      (node (ref "R2") (pin "1") (pinfunction "1_1") (pintype "passive"))
    )
    (net (code "60") (name "Net-(LED3-A)") (class "Default")
      (node (ref "LED3") (pin "2") (pinfunction "A_2") (pintype "bidirectional"))
      (node (ref "R3") (pin "1") (pinfunction "1_1") (pintype "passive"))
    )
    (net (code "61") (name "Net-(LED4-A)") (class "Default")
      (node (ref "LED4") (pin "2") (pinfunction "A_2") (pintype "bidirectional"))
      (node (ref "R4") (pin "1") (pinfunction "1_1") (pintype "passive"))
    )
    (net (code "62") (name "Net-(PS1-BST)") (class "Default")
      (node (ref "C3") (pin "2") (pinfunction "2_2") (pintype "passive"))
      (node (ref "PS1") (pin "6") (pinfunction "BST_6") (pintype "input"))
    )
    (net (code "63") (name "Net-(PS1-SW)") (class "Default")
      (node (ref "C3") (pin "1") (pinfunction "1_1") (pintype "passive"))
      (node (ref "L1") (pin "1") (pinfunction "1_1") (pintype "bidirectional"))
      (node (ref "PS1") (pin "5") (pinfunction "SW_5") (pintype "output"))
    )
    (net (code "64") (name "Net-(Q1-G)") (class "Default")
      (node (ref "Q1") (pin "1") (pinfunction "G_1") (pintype "bidirectional"))
      (node (ref "R5") (pin "1") (pinfunction "1_1") (pintype "passive"))
      (node (ref "R6") (pin "2") (pinfunction "2_2") (pintype "passive"))
    )
    (net (code "65") (name "Net-(R25-Pad1)") (class "Default")
      (node (ref "R25") (pin "1") (pinfunction "1_1") (pintype "passive"))
      (node (ref "R26") (pin "2") (pinfunction "2_2") (pintype "passive"))
    )
    (net (code "66") (name "unconnected-(IC1-CFETOFF-Pad29)") (class "Default")
      (node (ref "IC1") (pin "29") (pinfunction "CFETOFF_29") (pintype "bidirectional"))
    )
    (net (code "67") (name "unconnected-(IC1-DCHG-Pad31)") (class "Default")
      (node (ref "IC1") (pin "31") (pinfunction "DCHG_31") (pintype "bidirectional"))
    )
    (net (code "68") (name "unconnected-(IC1-DDSG-Pad32)") (class "Default")
      (node (ref "IC1") (pin "32") (pinfunction "DDSG_32") (pintype "bidirectional"))
    )
    (net (code "69") (name "unconnected-(IC1-DFETOFF-Pad30)") (class "Default")
      (node (ref "IC1") (pin "30") (pinfunction "DFETOFF_30") (pintype "bidirectional"))
    )
    (net (code "70") (name "unconnected-(IC1-FUSE-Pad38)") (class "Default")
      (node (ref "IC1") (pin "38") (pinfunction "FUSE_38") (pintype "bidirectional"))
    )
    (net (code "71") (name "unconnected-(IC1-HDQ-Pad28)") (class "Default")
      (node (ref "IC1") (pin "28") (pinfunction "HDQ_28") (pintype "bidirectional"))
    )
    (net (code "72") (name "unconnected-(IC1-NC_1-Pad1)") (class "Default")
      (node (ref "IC1") (pin "1") (pinfunction "NC_1_1") (pintype "bidirectional"))
    )
    (net (code "73") (name "unconnected-(IC1-NC_2-Pad3)") (class "Default")
      (node (ref "IC1") (pin "3") (pinfunction "NC_2_3") (pintype "bidirectional"))
    )
    (net (code "74") (name "unconnected-(IC1-NC_3-Pad5)") (class "Default")
      (node (ref "IC1") (pin "5") (pinfunction "NC_3_5") (pintype "bidirectional"))
    )
    (net (code "75") (name "unconnected-(IC1-NC_4-Pad7)") (class "Default")
      (node (ref "IC1") (pin "7") (pinfunction "NC_4_7") (pintype "bidirectional"))
    )
    (net (code "76") (name "unconnected-(IC1-NC_5-Pad9)") (class "Default")
      (node (ref "IC1") (pin "9") (pinfunction "NC_5_9") (pintype "bidirectional"))
    )
    (net (code "77") (name "unconnected-(IC1-NC_6-Pad11)") (class "Default")
      (node (ref "IC1") (pin "11") (pinfunction "NC_6_11") (pintype "bidirectional"))
    )
    (net (code "78") (name "unconnected-(IC1-NC_7-Pad19)") (class "Default")
      (node (ref "IC1") (pin "19") (pinfunction "NC_7_19") (pintype "bidirectional"))
    )
    (net (code "79") (name "unconnected-(IC1-NC_8-Pad44)") (class "Default")
      (node (ref "IC1") (pin "44") (pinfunction "NC_8_44") (pintype "bidirectional"))
    )
    (net (code "80") (name "unconnected-(IC1-PCHG-Pad40)") (class "Default")
      (node (ref "IC1") (pin "40") (pinfunction "PCHG_40") (pintype "bidirectional"))
    )
    (net (code "81") (name "unconnected-(IC1-PDSG-Pad39)") (class "Default")
      (node (ref "IC1") (pin "39") (pinfunction "PDSG_39") (pintype "bidirectional"))
    )
    (net (code "82") (name "unconnected-(J1-DAT1-PadP8)") (class "Default")
      (node (ref "J1") (pin "P8") (pinfunction "DAT1_P8") (pintype "bidirectional"))
    )
    (net (code "83") (name "unconnected-(J1-DAT2-PadP1)") (class "Default")
      (node (ref "J1") (pin "P1") (pinfunction "DAT2_P1") (pintype "bidirectional"))
    )
    (net (code "84") (name "unconnected-(U1-CLK-PadJ3-19)") (class "Default")
      (node (ref "U1") (pin "J3-19") (pinfunction "CLK_J3-19") (pintype "input"))
    )
    (net (code "85") (name "unconnected-(U1-CMD-PadJ2-18)") (class "Default")
      (node (ref "U1") (pin "J2-18") (pinfunction "CMD_J2-18") (pintype "bidirectional"))
    )
    (net (code "86") (name "unconnected-(U1-EN-PadJ2-2)") (class "Default")
      (node (ref "U1") (pin "J2-2") (pinfunction "EN_J2-2") (pintype "input"))
    )
    (net (code "87") (name "unconnected-(U1-IO0-PadJ3-14)") (class "Default")
      (node (ref "U1") (pin "J3-14") (pinfunction "IO0_J3-14") (pintype "bidirectional"))
    )
    (net (code "88") (name "unconnected-(U1-IO2-PadJ3-15)") (class "Default")
      (node (ref "U1") (pin "J3-15") (pinfunction "IO2_J3-15") (pintype "bidirectional"))
    )
    (net (code "89") (name "unconnected-(U1-IO12-PadJ2-13)") (class "Default")
      (node (ref "U1") (pin "J2-13") (pinfunction "IO12_J2-13") (pintype "bidirectional"))
    )
    (net (code "90") (name "unconnected-(U1-IO15-PadJ3-16)") (class "Default")
      (node (ref "U1") (pin "J3-16") (pinfunction "IO15_J3-16") (pintype "bidirectional"))
    )
    (net (code "91") (name "unconnected-(U1-IO32-PadJ2-7)") (class "Default")
      (node (ref "U1") (pin "J2-7") (pinfunction "IO32_J2-7") (pintype "bidirectional"))
    )
    (net (code "92") (name "unconnected-(U1-IO33-PadJ2-8)") (class "Default")
      (node (ref "U1") (pin "J2-8") (pinfunction "IO33_J2-8") (pintype "bidirectional"))
    )
    (net (code "93") (name "unconnected-(U1-IO34-PadJ2-5)") (class "Default")
      (node (ref "U1") (pin "J2-5") (pinfunction "IO34_J2-5") (pintype "bidirectional"))
    )
    (net (code "94") (name "unconnected-(U1-IO35-PadJ2-6)") (class "Default")
      (node (ref "U1") (pin "J2-6") (pinfunction "IO35_J2-6") (pintype "bidirectional"))
    )
    (net (code "95") (name "unconnected-(U1-RXD0-PadJ3-5)") (class "Default")
      (node (ref "U1") (pin "J3-5") (pinfunction "RXD0_J3-5") (pintype "input"))
    )
    (net (code "96") (name "unconnected-(U1-SD0-PadJ3-18)") (class "Default")
      (node (ref "U1") (pin "J3-18") (pinfunction "SD0_J3-18") (pintype "bidirectional"))
    )
    (net (code "97") (name "unconnected-(U1-SD1-PadJ3-17)") (class "Default")
      (node (ref "U1") (pin "J3-17") (pinfunction "SD1_J3-17") (pintype "bidirectional"))
    )
    (net (code "98") (name "unconnected-(U1-SD2-PadJ2-16)") (class "Default")
      (node (ref "U1") (pin "J2-16") (pinfunction "SD2_J2-16") (pintype "bidirectional"))
    )
    (net (code "99") (name "unconnected-(U1-SD3-PadJ2-17)") (class "Default")
      (node (ref "U1") (pin "J2-17") (pinfunction "SD3_J2-17") (pintype "bidirectional"))
    )
    (net (code "100") (name "unconnected-(U1-SENSOR_VN-PadJ2-4)") (class "Default")
      (node (ref "U1") (pin "J2-4") (pinfunction "SENSOR_VN_J2-4") (pintype "input"))
    )
    (net (code "101") (name "unconnected-(U1-SENSOR_VP-PadJ2-3)") (class "Default")
      (node (ref "U1") (pin "J2-3") (pinfunction "SENSOR_VP_J2-3") (pintype "input"))
    )
    (net (code "102") (name "unconnected-(U1-TXD0-PadJ3-4)") (class "Default")
      (node (ref "U1") (pin "J3-4") (pinfunction "TXD0_J3-4") (pintype "output"))
    )
    (net (code "103") (name "unconnected-(Z3-N.C.-Pad2)") (class "Default")
      (node (ref "Z3") (pin "2") (pinfunction "N.C._2") (pintype "no_connect"))
    )
    (net (code "104") (name "unconnected-(Z4-N.C.-Pad2)") (class "Default")
      (node (ref "Z4") (pin "2") (pinfunction "N.C._2") (pintype "no_connect"))
    )
  )
)
